# Camera-Connectors.net
KiCad netlist of a schematic drawn in Altium Designer
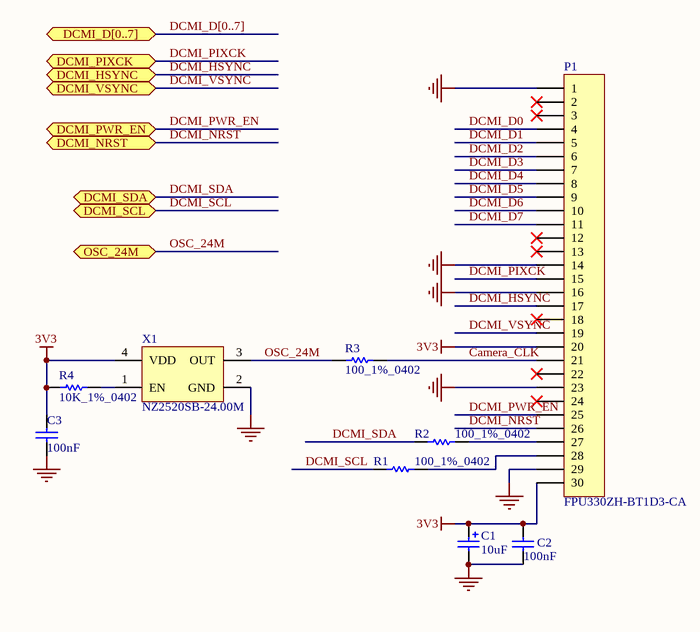
[diagram p0: Camera-Connectors.SchDoc]

(export (version "E")
  (design (tool "Eeschema 10.0.6"))
  (components
    (comp (ref "C1")
      (value "10uF")
      (footprint "TAN-A")
      (description "Polarized Capacitor,10uF,10V,10%,typeA,VISHAY")
      (libsource (lib "MCD_TOOLS") (part "Cap_10uF_POL_10%_TANA"))
    )
    (comp (ref "C2")
      (value "100nF")
      (footprint "0402C")
      (description "Capacitor,100nF,16V,X7R,10%,0402,YAGEO")
      (libsource (lib "MCD_TOOLS") (part "Cap_100nF_X7R_10%_0402"))
    )
    (comp (ref "C3")
      (value "100nF")
      (footprint "0402C")
      (description "Capacitor,100nF,16V,X7R,10%,0402,YAGEO")
      (libsource (lib "MCD_TOOLS") (part "Cap_100nF_X7R_10%_0402"))
    )
    (comp (ref "P1")
      (value "FPU330ZH-BT1D3-CA")
      (footprint "FPU330ZH-BT1D3-CA")
      (description "TOWNES -  Connector FFC/FPC ZIF 0.5mm 30 pins, Lower Contacts, 52892-3033")
      (libsource (lib "MCD_TOOLS") (part "FPU330ZH-BT1D3-CA"))
    )
    (comp (ref "R1")
      (value "100_1%_0402")
      (footprint "0402R")
      (description "Resistor,100,0402,1%,YAGEO")
      (libsource (lib "MCD_TOOLS") (part "Res_100_1%_0402"))
    )
    (comp (ref "R2")
      (value "100_1%_0402")
      (footprint "0402R")
      (description "Resistor,100,0402,1%,YAGEO")
      (libsource (lib "MCD_TOOLS") (part "Res_100_1%_0402"))
    )
    (comp (ref "R3")
      (value "100_1%_0402")
      (footprint "0402R")
      (description "Resistor,100,0402,1%,YAGEO")
      (libsource (lib "MCD_TOOLS") (part "Res_100_1%_0402"))
    )
    (comp (ref "R4")
      (value "10K_1%_0402")
      (footprint "0402R")
      (description "Resistor,10K,0402,1%,YAGEO")
      (libsource (lib "MCD_TOOLS") (part "Res_10K_1%_0402"))
    )
    (comp (ref "X1")
      (value "NZ2520SB-24.00M")
      (footprint "OSC_4SM_2R5X2R0")
      (description "Oscillator 24.00Mhz, -+50PPM, 3.3V, Temp -55 to +125°C")
      (libsource (lib "MCD_TOOLS") (part "OSC_24M_NZ2520SB"))
    )
  )
  (nets
    (net (code "1") (name "/Camera_CLK") (class "Default")
      (node (ref "P1") (pin "21") (pinfunction "21_21") (pintype "passive"))
      (node (ref "R3") (pin "2") (pinfunction "2_2") (pintype "passive"))
    )
    (net (code "2") (name "/DCMI_D0") (class "Default")
      (node (ref "P1") (pin "4") (pinfunction "4_4") (pintype "passive"))
    )
    (net (code "3") (name "/DCMI_D1") (class "Default")
      (node (ref "P1") (pin "5") (pinfunction "5_5") (pintype "passive"))
    )
    (net (code "4") (name "/DCMI_D2") (class "Default")
      (node (ref "P1") (pin "6") (pinfunction "6_6") (pintype "passive"))
    )
    (net (code "5") (name "/DCMI_D3") (class "Default")
      (node (ref "P1") (pin "7") (pinfunction "7_7") (pintype "passive"))
    )
    (net (code "6") (name "/DCMI_D4") (class "Default")
      (node (ref "P1") (pin "8") (pinfunction "8_8") (pintype "passive"))
    )
    (net (code "7") (name "/DCMI_D5") (class "Default")
      (node (ref "P1") (pin "9") (pinfunction "9_9") (pintype "passive"))
    )
    (net (code "8") (name "/DCMI_D6") (class "Default")
      (node (ref "P1") (pin "10") (pinfunction "10_10") (pintype "passive"))
    )
    (net (code "9") (name "/DCMI_D7") (class "Default")
      (node (ref "P1") (pin "11") (pinfunction "11_11") (pintype "passive"))
    )
    (net (code "11") (name "/DCMI_HSYNC") (class "Default")
      (node (ref "P1") (pin "17") (pinfunction "17_17") (pintype "passive"))
    )
    (net (code "12") (name "/DCMI_NRST") (class "Default")
      (node (ref "P1") (pin "26") (pinfunction "26_26") (pintype "passive"))
    )
    (net (code "13") (name "/DCMI_PIXCK") (class "Default")
      (node (ref "P1") (pin "15") (pinfunction "15_15") (pintype "passive"))
    )
    (net (code "14") (name "/DCMI_PWR_EN") (class "Default")
      (node (ref "P1") (pin "25") (pinfunction "25_25") (pintype "passive"))
    )
    (net (code "15") (name "/DCMI_SCL") (class "Default")
      (node (ref "R1") (pin "1") (pinfunction "1_1") (pintype "passive"))
    )
    (net (code "16") (name "/DCMI_SDA") (class "Default")
      (node (ref "R2") (pin "1") (pinfunction "1_1") (pintype "passive"))
    )
    (net (code "17") (name "/DCMI_VSYNC") (class "Default")
      (node (ref "P1") (pin "19") (pinfunction "19_19") (pintype "passive"))
    )
    (net (code "18") (name "/OSC_24M") (class "Default")
      (node (ref "R3") (pin "1") (pinfunction "1_1") (pintype "passive"))
      (node (ref "X1") (pin "3") (pinfunction "OUT_3") (pintype "passive"))
    )
    (net (code "19") (name "3V3") (class "Default")
      (node (ref "C1") (pin "1") (pinfunction "1_1") (pintype "passive"))
      (node (ref "C2") (pin "2") (pinfunction "2_2") (pintype "passive"))
      (node (ref "C3") (pin "2") (pinfunction "2_2") (pintype "passive"))
      (node (ref "P1") (pin "20") (pinfunction "20_20") (pintype "passive"))
      (node (ref "P1") (pin "30") (pinfunction "30_30") (pintype "passive"))
      (node (ref "R4") (pin "1") (pinfunction "1_1") (pintype "passive"))
      (node (ref "X1") (pin "4") (pinfunction "VDD_4") (pintype "passive"))
    )
    (net (code "20") (name "GND") (class "Default")
      (node (ref "C1") (pin "2") (pinfunction "2_2") (pintype "passive"))
      (node (ref "C2") (pin "1") (pinfunction "1_1") (pintype "passive"))
      (node (ref "C3") (pin "1") (pinfunction "1_1") (pintype "passive"))
      (node (ref "P1") (pin "1") (pinfunction "1_1") (pintype "passive"))
      (node (ref "P1") (pin "14") (pinfunction "14_14") (pintype "passive"))
      (node (ref "P1") (pin "16") (pinfunction "16_16") (pintype "passive"))
      (node (ref "P1") (pin "23") (pinfunction "23_23") (pintype "passive"))
      (node (ref "P1") (pin "29") (pinfunction "29_29") (pintype "passive"))
      (node (ref "X1") (pin "2") (pinfunction "GND_2") (pintype "passive"))
    )
    (net (code "21") (name "Net-(P1-Pad27)") (class "Default")
      (node (ref "P1") (pin "27") (pinfunction "27_27") (pintype "passive"))
      (node (ref "R2") (pin "2") (pinfunction "2_2") (pintype "passive"))
    )
    (net (code "22") (name "Net-(P1-Pad28)") (class "Default")
      (node (ref "P1") (pin "28") (pinfunction "28_28") (pintype "passive"))
      (node (ref "R1") (pin "2") (pinfunction "2_2") (pintype "passive"))
    )
    (net (code "23") (name "Net-(X1-EN)") (class "Default")
      (node (ref "R4") (pin "2") (pinfunction "2_2") (pintype "passive"))
      (node (ref "X1") (pin "1") (pinfunction "EN_1") (pintype "passive"))
    )
    (net (code "24") (name "unconnected-(P1-Pad2)") (class "Default")
      (node (ref "P1") (pin "2") (pinfunction "2_2") (pintype "passive+no_connect"))
    )
    (net (code "25") (name "unconnected-(P1-Pad3)") (class "Default")
      (node (ref "P1") (pin "3") (pinfunction "3_3") (pintype "passive+no_connect"))
    )
    (net (code "26") (name "unconnected-(P1-Pad12)") (class "Default")
      (node (ref "P1") (pin "12") (pinfunction "12_12") (pintype "passive+no_connect"))
    )
    (net (code "27") (name "unconnected-(P1-Pad13)") (class "Default")
      (node (ref "P1") (pin "13") (pinfunction "13_13") (pintype "passive+no_connect"))
    )
    (net (code "28") (name "unconnected-(P1-Pad18)") (class "Default")
      (node (ref "P1") (pin "18") (pinfunction "18_18") (pintype "passive+no_connect"))
    )
    (net (code "29") (name "unconnected-(P1-Pad22)") (class "Default")
      (node (ref "P1") (pin "22") (pinfunction "22_22") (pintype "passive+no_connect"))
    )
    (net (code "30") (name "unconnected-(P1-Pad24)") (class "Default")
      (node (ref "P1") (pin "24") (pinfunction "24_24") (pintype "passive+no_connect"))
    )
  )
)
